# ProDocument_CSPS-ATX12VO-NAK12S20_2023-0.net
KiCad netlist of a schematic drawn in EasyEDA Pro
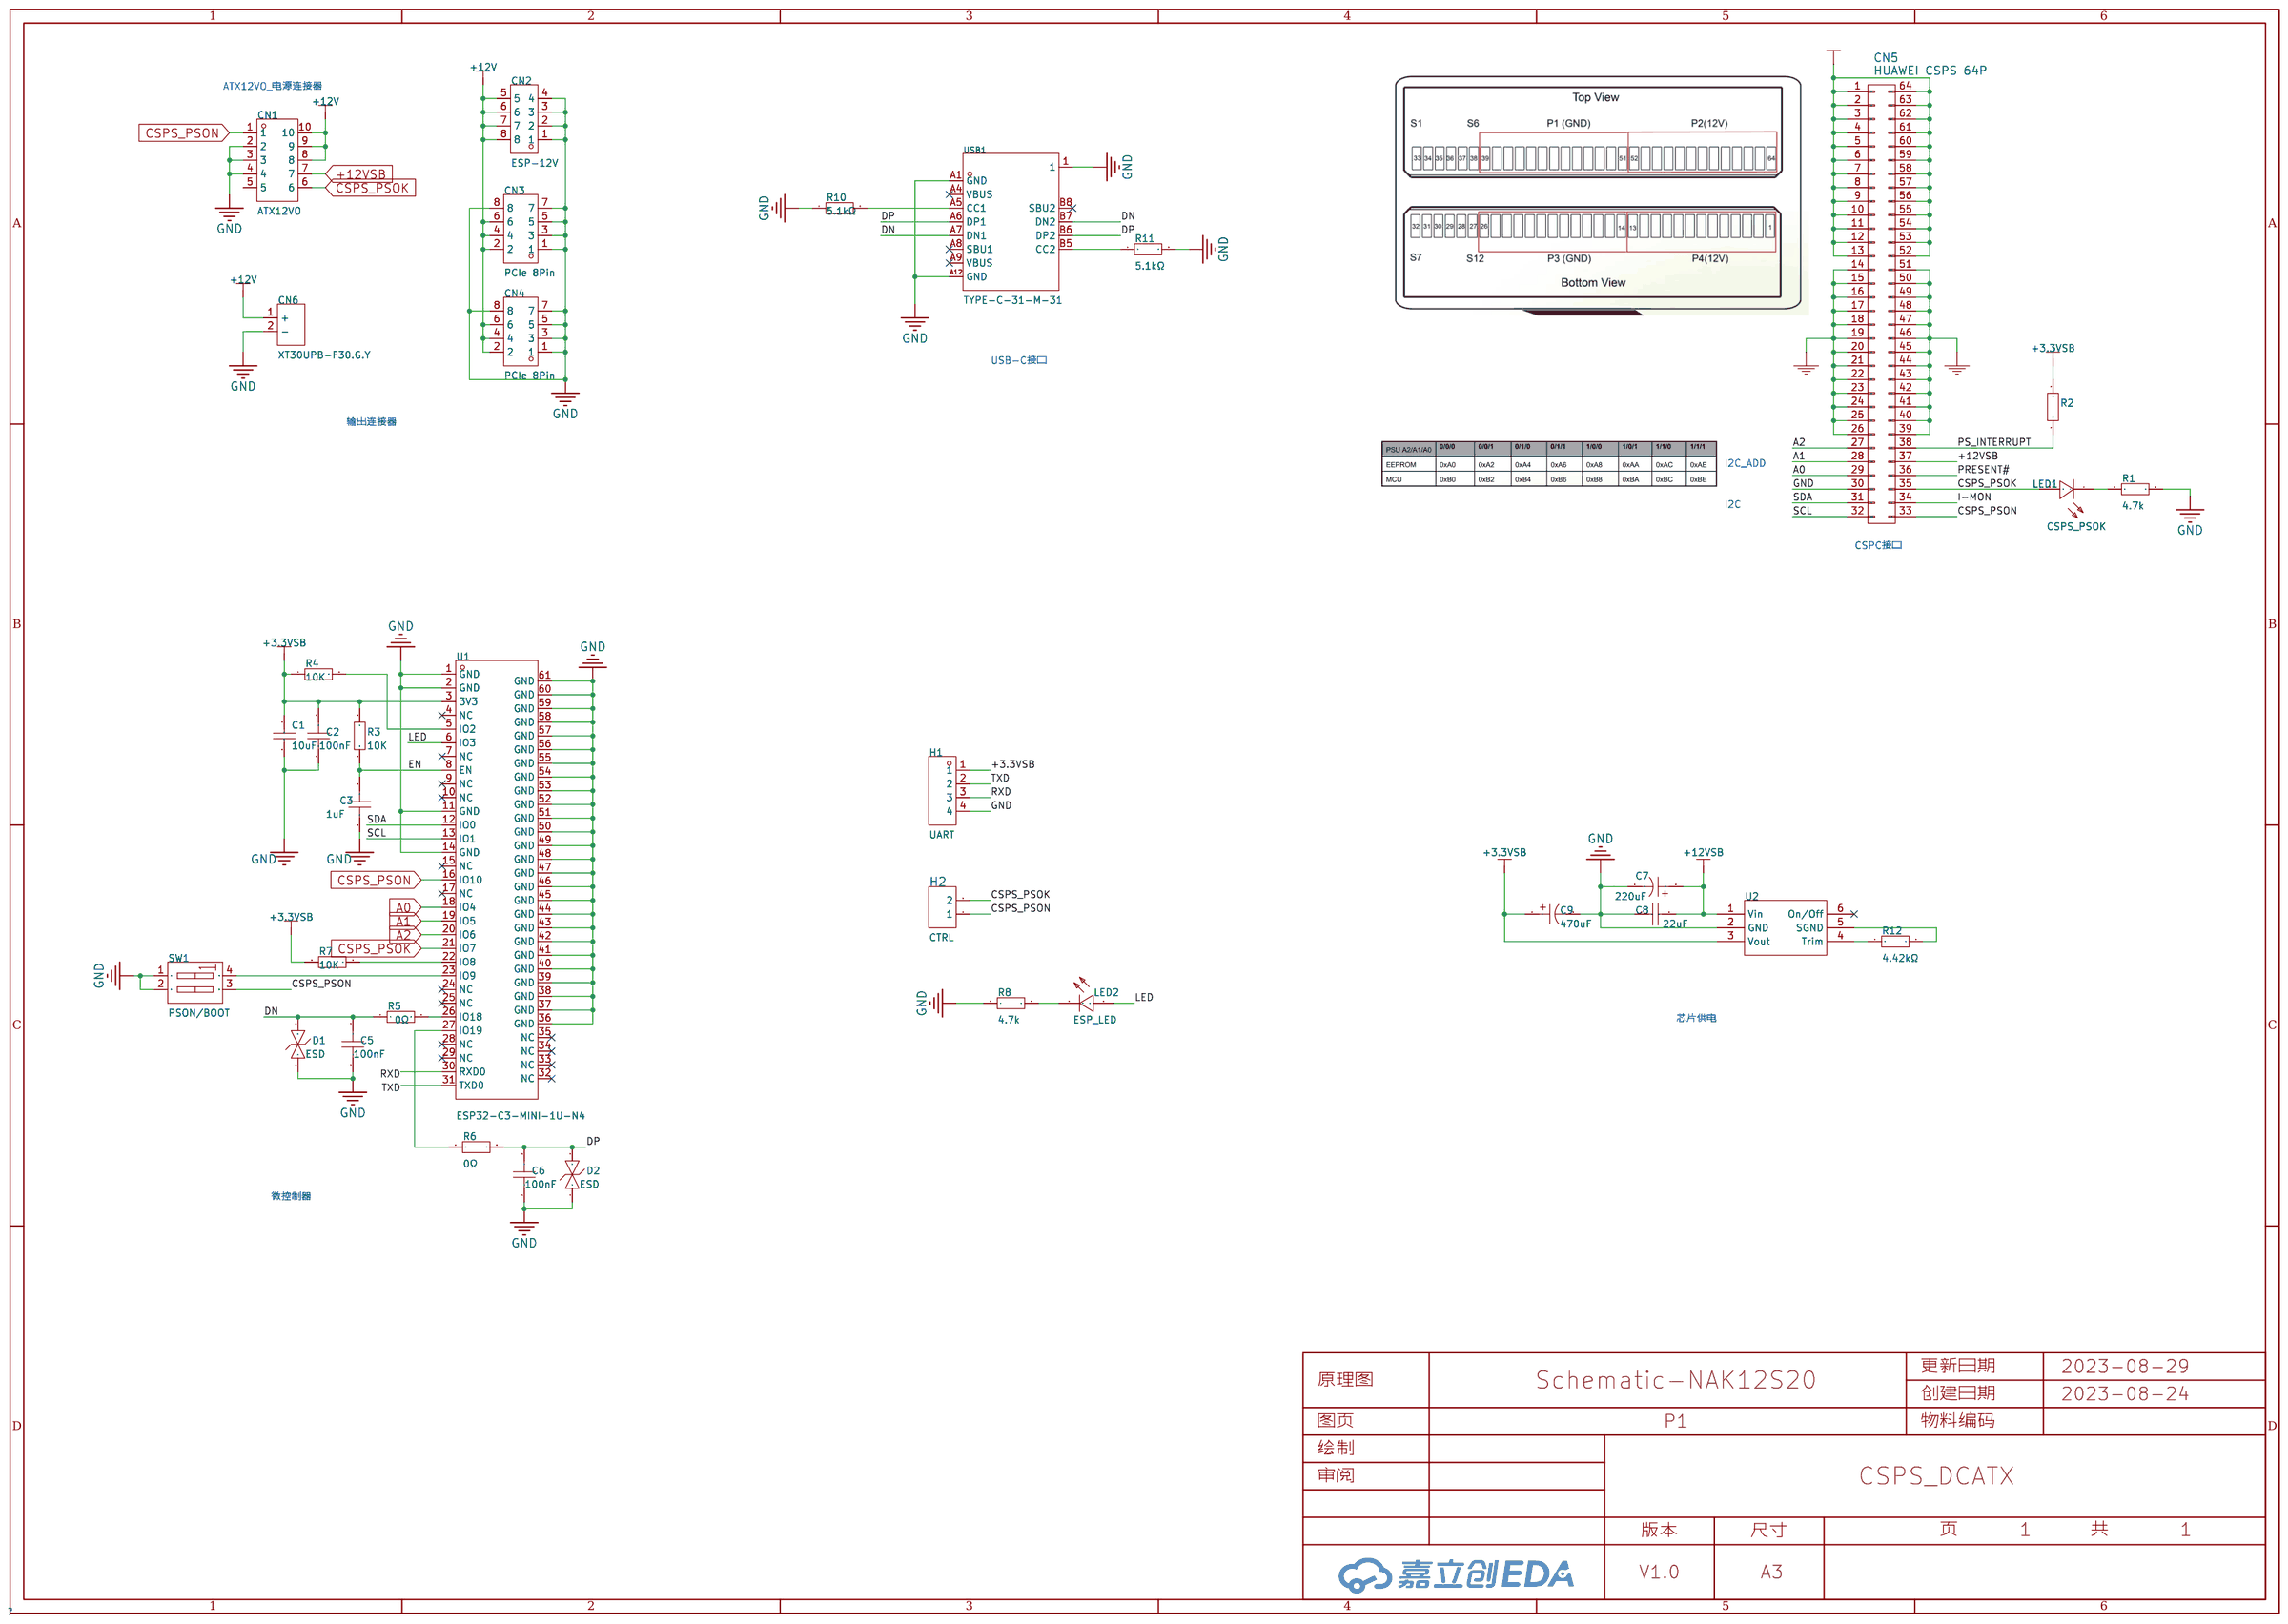
[diagram p0: schematic sheet]

(export (version "E")
  (design (tool "Eeschema 10.0.6"))
  (components
    (comp (ref "C1")
      (value "10uF")
      (footprint "easyedapro:C0805")
      (description "容值:10uF;精度:±10%;额定电压:25V;材质(温度系数):X5R;")
      (fields
        (field (name "Manufacturer Part") "CL21A106KAYNNNE")
        (field (name "Manufacturer") "SAMSUNG(三星)")
      )
      (libsource (lib "easyedapro") (part "CL21A106KAYNNNE"))
    )
    (comp (ref "C2")
      (value "100nF")
      (footprint "easyedapro:C0603")
      (libsource (lib "easyedapro") (part "CapAcitance"))
    )
    (comp (ref "C3")
      (value "1uF")
      (footprint "easyedapro:C0603")
      (libsource (lib "easyedapro") (part "CapAcitance"))
    )
    (comp (ref "C5")
      (value "100nF")
      (footprint "easyedapro:C0603")
      (libsource (lib "easyedapro") (part "CapAcitance"))
    )
    (comp (ref "C6")
      (value "100nF")
      (footprint "easyedapro:C0603")
      (libsource (lib "easyedapro") (part "CapAcitance"))
    )
    (comp (ref "C7")
      (value "220uF")
      (footprint "easyedapro:CAP-SMD_BD6.3-L6.6-W6.6-FD")
      (description "容值:220uF;精度:±20%;额定电压:16V;纹波电流:110mA@120Hz;等效串联电阻:-;")
      (fields
        (field (name "Manufacturer Part") "RVT220UF16V67RV0015")
        (field (name "Manufacturer") "KNSCHA(科尼盛)")
      )
      (libsource (lib "easyedapro") (part "RVT220UF16V67RV0015"))
    )
    (comp (ref "C8")
      (value "22uF")
      (footprint "easyedapro:C1206")
      (description "容值:22uF;精度:±10%;额定电压:25V;材质(温度系数):X5R;")
      (fields
        (field (name "Manufacturer Part") "CL31A226KAHNNNE")
        (field (name "Manufacturer") "SAMSUNG(三星)")
      )
      (libsource (lib "easyedapro") (part "CL31A226KAHNNNE"))
    )
    (comp (ref "C9")
      (value "470uF")
      (footprint "easyedapro:CAP-SMD_BD8.0-L8.3-W8.3-LS9.0-FD")
      (description "容值:470uF;额定电压:16V;工作寿命:2000hrs@105°C;")
      (fields
        (field (name "Manufacturer Part") "RVT470UF16V67RV0031")
        (field (name "Manufacturer") "KNSCHA(科尼盛)")
      )
      (libsource (lib "easyedapro") (part "RVT470UF16V67RV0031"))
    )
    (comp (ref "CN1")
      (value "ATX12VO")
      (footprint "easyedapro:CONN-TH_X9357WV-2-05-N2SN")
      (fields
        (field (name "Manufacturer Part") "X9357WV-2x05-N2SN")
        (field (name "Manufacturer") "XKB Connectivity(中国星坤)")
      )
      (libsource (lib "easyedapro") (part "X9357WV-2*05-N2SN"))
    )
    (comp (ref "CN2")
      (value "ESP-12V")
      (footprint "easyedapro:CONN-TH_39288080")
      (description "参考系列:-;间距:4.2mm;插针结构:2x4P;排数:2;每排PIN数:4;行距:4.2mm;公母:母型插口;安装方式:直插;额定电流:-;工作温度范围:-;")
      (fields (field (name "Manufacturer Part") "39288080") (field (name "Manufacturer") "MOLEX"))
      (libsource (lib "easyedapro") (part "39288080"))
    )
    (comp (ref "CN3")
      (value "PCIe 8Pin")
      (footprint "easyedapro:CONN-TH_8P-P4.20_CST_CS-1150-08D")
      (description "参考系列:-;间距:4.2mm;插针结构:2x4P;排数:2;每排PIN数:4;行距:4.2mm;公母:母型插口;安装方式:直插;额定电流:7A;工作温度范围:-40°C~+105°C;")
      (fields (field (name "Manufacturer Part") "CS-1150-08D") (field (name "Manufacturer") "CST(永丰盈)"))
      (libsource (lib "easyedapro") (part "CS-1150-08D"))
    )
    (comp (ref "CN4")
      (value "PCIe 8Pin")
      (footprint "easyedapro:CONN-TH_8P-P4.20_CST_CS-1150-08D")
      (description "参考系列:-;间距:4.2mm;插针结构:2x4P;排数:2;每排PIN数:4;行距:4.2mm;公母:母型插口;安装方式:直插;额定电流:7A;工作温度范围:-40°C~+105°C;")
      (fields (field (name "Manufacturer Part") "CS-1150-08D") (field (name "Manufacturer") "CST(永丰盈)"))
      (libsource (lib "easyedapro") (part "CS-1150-08D"))
    )
    (comp (ref "CN5")
      (value "HUAWEI CSPS 64P")
      (footprint "easyedapro:ATX 64P HP 野口64P直插")
      (libsource (lib "easyedapro") (part "HP CSPS ATX 64P"))
    )
    (comp (ref "CN6")
      (value "XT30UPB-F30.G.Y")
      (footprint "easyedapro:CONN-TH_XT30UPB-F")
      (description "模型插头连接器")
      (fields (field (name "Manufacturer") "AMASS(艾迈斯)"))
      (libsource (lib "easyedapro") (part "XT30UPB-F"))
    )
    (comp (ref "D1")
      (value "ESD")
      (footprint "easyedapro:SOD-882_L1.0-W0.6-BI")
      (description "极性:-;反向关断电压（典型值）:5V (Max);击穿电压（最小值）:6V;箝位电压:25V;峰值脉冲电流（10/1000us）:2.5A (8/20us);")
      (fields (field (name "Manufacturer Part") "ESD05V88D-LC") (field (name "Manufacturer") "SOCAY(硕凯)"))
      (libsource (lib "easyedapro") (part "ESD05V88D-LC"))
    )
    (comp (ref "D2")
      (value "ESD")
      (footprint "easyedapro:SOD-882_L1.0-W0.6-BI")
      (description "极性:-;反向关断电压（典型值）:5V (Max);击穿电压（最小值）:6V;箝位电压:25V;峰值脉冲电流（10/1000us）:2.5A (8/20us);")
      (fields (field (name "Manufacturer Part") "ESD05V88D-LC") (field (name "Manufacturer") "SOCAY(硕凯)"))
      (libsource (lib "easyedapro") (part "ESD05V88D-LC"))
    )
    (comp (ref "H1")
      (value "UART")
      (footprint "easyedapro:HDR-TH_4P-P2.54-V-F")
      (libsource (lib "easyedapro") (part "2.54-1*4P母"))
    )
    (comp (ref "H2")
      (value "CTRL")
      (footprint "easyedapro:HDR-TH_2P-P2.54-V-F")
      (libsource (lib "easyedapro") (part "Header-Female-2.54_1x2"))
    )
    (comp (ref "LED1")
      (value "CSPS_PSOK")
      (footprint "easyedapro:LED0603-RD_GREEN")
      (fields (field (name "Manufacturer Part") "LED-0603G-FZ_GREEN"))
      (libsource (lib "easyedapro") (part "LED-0603G-FZ_GREEN"))
    )
    (comp (ref "LED2")
      (value "ESP_LED")
      (footprint "easyedapro:LED0603-RD")
      (description "发光颜色:翠绿;二极管配置:-;主波长:520nm~535nm;色温:-;功率:110mW;安装方式:-;")
      (fields
        (field (name "Manufacturer Part") "19-217/GHC-YR1S2/3T")
        (field (name "Manufacturer") "EVERLIGHT(亿光)")
      )
      (libsource (lib "easyedapro") (part "19-217/GHC-YR1S2/3T"))
    )
    (comp (ref "R1") (value "4.7k") (footprint "easyedapro:R0603") (libsource (lib "easyedapro") (part "电阻")))
    (comp (ref "R2") (value "4.7k") (footprint "easyedapro:R0603") (libsource (lib "easyedapro") (part "电阻")))
    (comp (ref "R3") (value "10K") (footprint "easyedapro:R0603") (libsource (lib "easyedapro") (part "电阻")))
    (comp (ref "R4") (value "10K") (footprint "easyedapro:R0603") (libsource (lib "easyedapro") (part "电阻")))
    (comp (ref "R5")
      (value "0Ω")
      (footprint "easyedapro:R0603")
      (description "电阻类型:厚膜电阻;阻值:0Ω;精度:±1%;功率:100mW;")
      (fields
        (field (name "Manufacturer Part") "0603WAF0000T5E")
        (field (name "Manufacturer") "UNI-ROYAL(厚声)")
      )
      (libsource (lib "easyedapro") (part "0603WAF0000T5E"))
    )
    (comp (ref "R6")
      (value "0Ω")
      (footprint "easyedapro:R0603")
      (description "电阻类型:厚膜电阻;阻值:0Ω;精度:±1%;功率:100mW;")
      (fields
        (field (name "Manufacturer Part") "0603WAF0000T5E")
        (field (name "Manufacturer") "UNI-ROYAL(厚声)")
      )
      (libsource (lib "easyedapro") (part "0603WAF0000T5E"))
    )
    (comp (ref "R7") (value "10K") (footprint "easyedapro:R0603") (libsource (lib "easyedapro") (part "电阻")))
    (comp (ref "R8") (value "4.7k") (footprint "easyedapro:R0603") (libsource (lib "easyedapro") (part "电阻")))
    (comp (ref "R10")
      (value "5.1kΩ")
      (footprint "easyedapro:R0603")
      (description "电阻类型:厚膜电阻;阻值:5.1kΩ;精度:±1%;功率:100mW;")
      (fields
        (field (name "Manufacturer Part") "0603WAF5101T5E")
        (field (name "Manufacturer") "UNI-ROYAL(厚声)")
      )
      (libsource (lib "easyedapro") (part "0603WAF5101T5E"))
    )
    (comp (ref "R11")
      (value "5.1kΩ")
      (footprint "easyedapro:R0603")
      (description "电阻类型:厚膜电阻;阻值:5.1kΩ;精度:±1%;功率:100mW;")
      (fields
        (field (name "Manufacturer Part") "0603WAF5101T5E")
        (field (name "Manufacturer") "UNI-ROYAL(厚声)")
      )
      (libsource (lib "easyedapro") (part "0603WAF5101T5E"))
    )
    (comp (ref "R12")
      (value "4.42kΩ")
      (footprint "easyedapro:R0603")
      (description "电阻类型:厚膜电阻;阻值:4.42kΩ;精度:±1%;功率:100mW;")
      (fields
        (field (name "Manufacturer Part") "0603WAF4421T5E")
        (field (name "Manufacturer") "UNI-ROYAL(厚声)")
      )
      (libsource (lib "easyedapro") (part "0603WAF4421T5E"))
    )
    (comp (ref "SW1")
      (value "PSON/BOOT")
      (footprint "easyedapro:SW-SMD_4P-L6.0-W5.1-P2.54-LS9.3-BL")
      (description "类型:平拨，凸起式;电路结构:单刀单掷;开关位数:2;引脚间距:2.54mm;颜色:黑色;")
      (fields (field (name "Manufacturer Part") "DSIC02LSGET") (field (name "Manufacturer") "YE"))
      (libsource (lib "easyedapro") (part "DSIC02LSGET"))
    )
    (comp (ref "U1")
      (value "ESP32-C3-MINI-1U-N4")
      (footprint "easyedapro:WIFIM-SMD_61P-L13.2-W12.5-P0.80")
      (fields (field (name "Manufacturer") "ESPRESSIF(乐鑫)"))
      (libsource (lib "easyedapro") (part "ESP32-C3-MINI-1U-N4"))
    )
    (comp (ref "U2")
      (value "~")
      (footprint "easyedapro:NAK12S20-C")
      (description "华为降压模块")
      (fields (field (name "Manufacturer") "HUAWEI"))
      (libsource (lib "easyedapro") (part "NAK12S20-C"))
    )
    (comp (ref "USB1")
      (value "TYPE-C-31-M-31")
      (footprint "easyedapro:USB-C-SMD_TYPE-C-31-M-31")
      (description "连接器类型:Type-C;标准:-;公母:母座;触点数量:16;端口数量:1;安装方式:卧贴;额定电流 - 电源:5A;工作温度范围:-30°C~+80°C;")
      (fields (field (name "Manufacturer") "韩国韩荣"))
      (libsource (lib "easyedapro") (part "TYPE-C-31-M-31"))
    )
  )
  (nets
    (net (code "1") (name "+3.3VSB") (class "Default")
      (node (ref "C1") (pin "2") (pinfunction "2_2") (pintype "input"))
      (node (ref "C2") (pin "2") (pinfunction "2_2") (pintype "input"))
      (node (ref "C9") (pin "1") (pinfunction "1_1") (pintype "input"))
      (node (ref "H1") (pin "1") (pinfunction "1_1") (pintype "input"))
      (node (ref "R2") (pin "2") (pinfunction "2_2") (pintype "input"))
      (node (ref "R3") (pin "2") (pinfunction "2_2") (pintype "input"))
      (node (ref "R4") (pin "1") (pinfunction "1_1") (pintype "input"))
      (node (ref "R7") (pin "1") (pinfunction "1_1") (pintype "input"))
      (node (ref "U1") (pin "3") (pinfunction "3V3_3") (pintype "input"))
      (node (ref "U2") (pin "3") (pinfunction "Vout_3") (pintype "input"))
    )
    (net (code "2") (name "+12V") (class "Default")
      (node (ref "CN1") (pin "10") (pinfunction "10_10") (pintype "input"))
      (node (ref "CN1") (pin "8") (pinfunction "8_8") (pintype "input"))
      (node (ref "CN1") (pin "9") (pinfunction "9_9") (pintype "input"))
      (node (ref "CN2") (pin "5") (pinfunction "5_5") (pintype "input"))
      (node (ref "CN2") (pin "6") (pinfunction "6_6") (pintype "input"))
      (node (ref "CN2") (pin "7") (pinfunction "7_7") (pintype "input"))
      (node (ref "CN2") (pin "8") (pinfunction "8_8") (pintype "input"))
      (node (ref "CN3") (pin "2") (pinfunction "2_2") (pintype "input"))
      (node (ref "CN3") (pin "4") (pinfunction "4_4") (pintype "input"))
      (node (ref "CN3") (pin "6") (pinfunction "6_6") (pintype "input"))
      (node (ref "CN4") (pin "2") (pinfunction "2_2") (pintype "input"))
      (node (ref "CN4") (pin "4") (pinfunction "4_4") (pintype "input"))
      (node (ref "CN4") (pin "6") (pinfunction "6_6") (pintype "input"))
      (node (ref "CN5") (pin "1") (pinfunction "Pin_1_1") (pintype "input"))
      (node (ref "CN5") (pin "10") (pinfunction "Pin_10_10") (pintype "input"))
      (node (ref "CN5") (pin "11") (pinfunction "Pin_11_11") (pintype "input"))
      (node (ref "CN5") (pin "12") (pinfunction "Pin_12_12") (pintype "input"))
      (node (ref "CN5") (pin "13") (pinfunction "Pin_13_13") (pintype "input"))
      (node (ref "CN5") (pin "2") (pinfunction "Pin_2_2") (pintype "input"))
      (node (ref "CN5") (pin "3") (pinfunction "Pin_3_3") (pintype "input"))
      (node (ref "CN5") (pin "4") (pinfunction "Pin_4_4") (pintype "input"))
      (node (ref "CN5") (pin "5") (pinfunction "Pin_5_5") (pintype "input"))
      (node (ref "CN5") (pin "52") (pinfunction "Pin_52_52") (pintype "input"))
      (node (ref "CN5") (pin "53") (pinfunction "Pin_53_53") (pintype "input"))
      (node (ref "CN5") (pin "54") (pinfunction "Pin_54_54") (pintype "input"))
      (node (ref "CN5") (pin "55") (pinfunction "Pin_55_55") (pintype "input"))
      (node (ref "CN5") (pin "56") (pinfunction "Pin_56_56") (pintype "input"))
      (node (ref "CN5") (pin "57") (pinfunction "Pin_57_57") (pintype "input"))
      (node (ref "CN5") (pin "58") (pinfunction "Pin_58_58") (pintype "input"))
      (node (ref "CN5") (pin "59") (pinfunction "Pin_59_59") (pintype "input"))
      (node (ref "CN5") (pin "6") (pinfunction "Pin_6_6") (pintype "input"))
      (node (ref "CN5") (pin "60") (pinfunction "Pin_60_60") (pintype "input"))
      (node (ref "CN5") (pin "61") (pinfunction "Pin_61_61") (pintype "input"))
      (node (ref "CN5") (pin "62") (pinfunction "Pin_62_62") (pintype "input"))
      (node (ref "CN5") (pin "63") (pinfunction "Pin_63_63") (pintype "input"))
      (node (ref "CN5") (pin "64") (pinfunction "Pin_64_64") (pintype "input"))
      (node (ref "CN5") (pin "7") (pinfunction "Pin_7_7") (pintype "input"))
      (node (ref "CN5") (pin "8") (pinfunction "Pin_8_8") (pintype "input"))
      (node (ref "CN5") (pin "9") (pinfunction "Pin_9_9") (pintype "input"))
      (node (ref "CN6") (pin "1") (pinfunction "+_1") (pintype "input"))
    )
    (net (code "3") (name "+12VSB") (class "Default")
      (node (ref "C7") (pin "1") (pinfunction "1_1") (pintype "input"))
      (node (ref "C8") (pin "2") (pinfunction "2_2") (pintype "input"))
      (node (ref "CN1") (pin "7") (pinfunction "7_7") (pintype "input"))
      (node (ref "CN5") (pin "37") (pinfunction "+12VSB_37") (pintype "input"))
      (node (ref "U2") (pin "1") (pinfunction "Vin_1") (pintype "input"))
    )
    (net (code "4") (name "/DN") (class "Default")
      (node (ref "C5") (pin "2") (pinfunction "2_2") (pintype "input"))
      (node (ref "D1") (pin "2") (pinfunction "2_2") (pintype "input"))
      (node (ref "R5") (pin "1") (pinfunction "1_1") (pintype "input"))
      (node (ref "USB1") (pin "A7") (pinfunction "DN1_A7") (pintype "input"))
      (node (ref "USB1") (pin "B7") (pinfunction "DN2_B7") (pintype "input"))
    )
    (net (code "5") (name "/DP") (class "Default")
      (node (ref "C6") (pin "2") (pinfunction "2_2") (pintype "input"))
      (node (ref "D2") (pin "2") (pinfunction "2_2") (pintype "input"))
      (node (ref "R6") (pin "2") (pinfunction "2_2") (pintype "input"))
      (node (ref "USB1") (pin "A6") (pinfunction "DP1_A6") (pintype "input"))
      (node (ref "USB1") (pin "B6") (pinfunction "DP2_B6") (pintype "input"))
    )
    (net (code "6") (name "/EN") (class "Default")
      (node (ref "C3") (pin "2") (pinfunction "2_2") (pintype "input"))
      (node (ref "R3") (pin "1") (pinfunction "1_1") (pintype "input"))
      (node (ref "U1") (pin "8") (pinfunction "EN_8") (pintype "input"))
    )
    (net (code "7") (name "/I-MON") (class "Default")
      (node (ref "CN5") (pin "34") (pinfunction "sda_34") (pintype "input"))
    )
    (net (code "8") (name "/LED") (class "Default")
      (node (ref "LED2") (pin "2") (pinfunction "A_2") (pintype "input"))
      (node (ref "U1") (pin "6") (pinfunction "IO3_6") (pintype "input"))
    )
    (net (code "9") (name "/PRESENT#") (class "Default")
      (node (ref "CN5") (pin "36") (pinfunction "PRESENT_36") (pintype "input"))
    )
    (net (code "10") (name "/PS_INTERRUPT") (class "Default")
      (node (ref "CN5") (pin "38") (pinfunction "pin_38_38") (pintype "input"))
      (node (ref "R2") (pin "1") (pinfunction "1_1") (pintype "input"))
    )
    (net (code "11") (name "/RXD") (class "Default")
      (node (ref "H1") (pin "3") (pinfunction "3_3") (pintype "input"))
      (node (ref "U1") (pin "30") (pinfunction "RXD0_30") (pintype "input"))
    )
    (net (code "12") (name "/SCL") (class "Default")
      (node (ref "CN5") (pin "32") (pinfunction "CSPS-PSON_32") (pintype "input"))
      (node (ref "U1") (pin "13") (pinfunction "IO1_13") (pintype "input"))
    )
    (net (code "13") (name "/SDA") (class "Default")
      (node (ref "CN5") (pin "31") (pinfunction "Pin_31_31") (pintype "input"))
      (node (ref "U1") (pin "12") (pinfunction "IO0_12") (pintype "input"))
    )
    (net (code "14") (name "/TXD") (class "Default")
      (node (ref "H1") (pin "2") (pinfunction "2_2") (pintype "input"))
      (node (ref "U1") (pin "31") (pinfunction "TXD0_31") (pintype "input"))
    )
    (net (code "15") (name "A0") (class "Default")
      (node (ref "CN5") (pin "29") (pinfunction "PRESENT_29") (pintype "input"))
      (node (ref "U1") (pin "18") (pinfunction "IO4_18") (pintype "input"))
    )
    (net (code "16") (name "A1") (class "Default")
      (node (ref "CN5") (pin "28") (pinfunction "+12VSB_28") (pintype "input"))
      (node (ref "U1") (pin "19") (pinfunction "IO5_19") (pintype "input"))
    )
    (net (code "17") (name "A2") (class "Default")
      (node (ref "CN5") (pin "27") (pinfunction "PWOK_27") (pintype "input"))
      (node (ref "U1") (pin "20") (pinfunction "IO6_20") (pintype "input"))
    )
    (net (code "18") (name "CSPS_PSOK") (class "Default")
      (node (ref "CN1") (pin "6") (pinfunction "6_6") (pintype "input"))
      (node (ref "CN5") (pin "35") (pinfunction "I2C-GND_35") (pintype "input"))
      (node (ref "H2") (pin "2") (pinfunction "2_2") (pintype "input"))
      (node (ref "LED1") (pin "2") (pinfunction "+_2") (pintype "input"))
      (node (ref "U1") (pin "21") (pinfunction "IO7_21") (pintype "input"))
    )
    (net (code "19") (name "CSPS_PSON") (class "Default")
      (node (ref "CN1") (pin "1") (pinfunction "1_1") (pintype "input"))
      (node (ref "CN5") (pin "33") (pinfunction "scl_33") (pintype "input"))
      (node (ref "H2") (pin "1") (pinfunction "1_1") (pintype "input"))
      (node (ref "SW1") (pin "3") (pinfunction "B2_3") (pintype "input"))
      (node (ref "U1") (pin "16") (pinfunction "IO10_16") (pintype "input"))
    )
    (net (code "20") (name "GND") (class "Default")
      (node (ref "C1") (pin "1") (pinfunction "1_1") (pintype "input"))
      (node (ref "C2") (pin "1") (pinfunction "1_1") (pintype "input"))
      (node (ref "C3") (pin "1") (pinfunction "1_1") (pintype "input"))
      (node (ref "C5") (pin "1") (pinfunction "1_1") (pintype "input"))
      (node (ref "C6") (pin "1") (pinfunction "1_1") (pintype "input"))
      (node (ref "C7") (pin "2") (pinfunction "2_2") (pintype "input"))
      (node (ref "C8") (pin "1") (pinfunction "1_1") (pintype "input"))
      (node (ref "C9") (pin "2") (pinfunction "2_2") (pintype "input"))
      (node (ref "CN1") (pin "2") (pinfunction "2_2") (pintype "input"))
      (node (ref "CN1") (pin "3") (pinfunction "3_3") (pintype "input"))
      (node (ref "CN1") (pin "4") (pinfunction "4_4") (pintype "input"))
      (node (ref "CN2") (pin "1") (pinfunction "1_1") (pintype "input"))
      (node (ref "CN2") (pin "2") (pinfunction "2_2") (pintype "input"))
      (node (ref "CN2") (pin "3") (pinfunction "3_3") (pintype "input"))
      (node (ref "CN2") (pin "4") (pinfunction "4_4") (pintype "input"))
      (node (ref "CN3") (pin "1") (pinfunction "1_1") (pintype "input"))
      (node (ref "CN3") (pin "3") (pinfunction "3_3") (pintype "input"))
      (node (ref "CN3") (pin "5") (pinfunction "5_5") (pintype "input"))
      (node (ref "CN3") (pin "7") (pinfunction "7_7") (pintype "input"))
      (node (ref "CN3") (pin "8") (pinfunction "8_8") (pintype "input"))
      (node (ref "CN4") (pin "1") (pinfunction "1_1") (pintype "input"))
      (node (ref "CN4") (pin "3") (pinfunction "3_3") (pintype "input"))
      (node (ref "CN4") (pin "5") (pinfunction "5_5") (pintype "input"))
      (node (ref "CN4") (pin "7") (pinfunction "7_7") (pintype "input"))
      (node (ref "CN4") (pin "8") (pinfunction "8_8") (pintype "input"))
      (node (ref "CN5") (pin "14") (pinfunction "Pin_14_14") (pintype "input"))
      (node (ref "CN5") (pin "15") (pinfunction "Pin_15_15") (pintype "input"))
      (node (ref "CN5") (pin "16") (pinfunction "Pin_16_16") (pintype "input"))
      (node (ref "CN5") (pin "17") (pinfunction "Pin_17_17") (pintype "input"))
      (node (ref "CN5") (pin "18") (pinfunction "Pin_18_18") (pintype "input"))
      (node (ref "CN5") (pin "19") (pinfunction "Pin_19_19") (pintype "input"))
      (node (ref "CN5") (pin "20") (pinfunction "Pin_20_20") (pintype "input"))
      (node (ref "CN5") (pin "21") (pinfunction "Pin_21_21") (pintype "input"))
      (node (ref "CN5") (pin "22") (pinfunction "Pin_22_22") (pintype "input"))
      (node (ref "CN5") (pin "23") (pinfunction "Pin_23_23") (pintype "input"))
      (node (ref "CN5") (pin "24") (pinfunction "Pin_24_24") (pintype "input"))
      (node (ref "CN5") (pin "25") (pinfunction "Pin_25_25") (pintype "input"))
      (node (ref "CN5") (pin "26") (pinfunction "Pin_26_26") (pintype "input"))
      (node (ref "CN5") (pin "30") (pinfunction "CSPS-PSOK_30") (pintype "input"))
      (node (ref "CN5") (pin "39") (pinfunction "Pin_39_39") (pintype "input"))
      (node (ref "CN5") (pin "40") (pinfunction "Pin_40_40") (pintype "input"))
      (node (ref "CN5") (pin "41") (pinfunction "Pin_41_41") (pintype "input"))
      (node (ref "CN5") (pin "42") (pinfunction "Pin_42_42") (pintype "input"))
      (node (ref "CN5") (pin "43") (pinfunction "Pin_43_43") (pintype "input"))
      (node (ref "CN5") (pin "44") (pinfunction "Pin_44_44") (pintype "input"))
      (node (ref "CN5") (pin "45") (pinfunction "Pin_45_45") (pintype "input"))
      (node (ref "CN5") (pin "46") (pinfunction "Pin_46_46") (pintype "input"))
      (node (ref "CN5") (pin "47") (pinfunction "Pin_47_47") (pintype "input"))
      (node (ref "CN5") (pin "48") (pinfunction "Pin_48_48") (pintype "input"))
      (node (ref "CN5") (pin "49") (pinfunction "Pin_49_49") (pintype "input"))
      (node (ref "CN5") (pin "50") (pinfunction "Pin_50_50") (pintype "input"))
      (node (ref "CN5") (pin "51") (pinfunction "Pin_51_51") (pintype "input"))
      (node (ref "CN6") (pin "2") (pinfunction "-_2") (pintype "input"))
      (node (ref "D1") (pin "1") (pinfunction "1_1") (pintype "input"))
      (node (ref "D2") (pin "1") (pinfunction "1_1") (pintype "input"))
      (node (ref "H1") (pin "4") (pinfunction "4_4") (pintype "input"))
      (node (ref "R1") (pin "2") (pinfunction "2_2") (pintype "input"))
      (node (ref "R10") (pin "1") (pinfunction "1_1") (pintype "input"))
      (node (ref "R11") (pin "2") (pinfunction "2_2") (pintype "input"))
      (node (ref "R8") (pin "1") (pinfunction "1_1") (pintype "input"))
      (node (ref "SW1") (pin "1") (pinfunction "A1_1") (pintype "input"))
      (node (ref "SW1") (pin "2") (pinfunction "A2_2") (pintype "input"))
      (node (ref "U1") (pin "1") (pinfunction "GND_1") (pintype "input"))
      (node (ref "U1") (pin "11") (pinfunction "GND_11") (pintype "input"))
      (node (ref "U1") (pin "14") (pinfunction "GND_14") (pintype "input"))
      (node (ref "U1") (pin "2") (pinfunction "GND_2") (pintype "input"))
      (node (ref "U1") (pin "36") (pinfunction "GND_36") (pintype "input"))
      (node (ref "U1") (pin "37") (pinfunction "GND_37") (pintype "input"))
      (node (ref "U1") (pin "38") (pinfunction "GND_38") (pintype "input"))
      (node (ref "U1") (pin "39") (pinfunction "GND_39") (pintype "input"))
      (node (ref "U1") (pin "40") (pinfunction "GND_40") (pintype "input"))
      (node (ref "U1") (pin "41") (pinfunction "GND_41") (pintype "input"))
      (node (ref "U1") (pin "42") (pinfunction "GND_42") (pintype "input"))
      (node (ref "U1") (pin "43") (pinfunction "GND_43") (pintype "input"))
      (node (ref "U1") (pin "44") (pinfunction "GND_44") (pintype "input"))
      (node (ref "U1") (pin "45") (pinfunction "GND_45") (pintype "input"))
      (node (ref "U1") (pin "46") (pinfunction "GND_46") (pintype "input"))
      (node (ref "U1") (pin "47") (pinfunction "GND_47") (pintype "input"))
      (node (ref "U1") (pin "48") (pinfunction "GND_48") (pintype "input"))
      (node (ref "U1") (pin "49") (pinfunction "GND_49") (pintype "input"))
      (node (ref "U1") (pin "50") (pinfunction "GND_50") (pintype "input"))
      (node (ref "U1") (pin "51") (pinfunction "GND_51") (pintype "input"))
      (node (ref "U1") (pin "52") (pinfunction "GND_52") (pintype "input"))
      (node (ref "U1") (pin "53") (pinfunction "GND_53") (pintype "input"))
      (node (ref "U1") (pin "54") (pinfunction "GND_54") (pintype "input"))
      (node (ref "U1") (pin "55") (pinfunction "GND_55") (pintype "input"))
      (node (ref "U1") (pin "56") (pinfunction "GND_56") (pintype "input"))
      (node (ref "U1") (pin "57") (pinfunction "GND_57") (pintype "input"))
      (node (ref "U1") (pin "58") (pinfunction "GND_58") (pintype "input"))
      (node (ref "U1") (pin "59") (pinfunction "GND_59") (pintype "input"))
      (node (ref "U1") (pin "60") (pinfunction "GND_60") (pintype "input"))
      (node (ref "U1") (pin "61") (pinfunction "GND_61") (pintype "input"))
      (node (ref "U2") (pin "2") (pinfunction "GND_2") (pintype "input"))
      (node (ref "USB1") (pin "1") (pinfunction "1_1") (pintype "input"))
      (node (ref "USB1") (pin "A1") (pinfunction "GND_A1") (pintype "input"))
      (node (ref "USB1") (pin "A12") (pinfunction "GND_A12") (pintype "input"))
    )
    (net (code "21") (name "Net-(LED1--)") (class "Default")
      (node (ref "LED1") (pin "1") (pinfunction "-_1") (pintype "input"))
      (node (ref "R1") (pin "1") (pinfunction "1_1") (pintype "input"))
    )
    (net (code "22") (name "Net-(LED2-C)") (class "Default")
      (node (ref "LED2") (pin "1") (pinfunction "C_1") (pintype "input"))
      (node (ref "R8") (pin "2") (pinfunction "2_2") (pintype "input"))
    )
    (net (code "23") (name "Net-(SW1-B1)") (class "Default")
      (node (ref "SW1") (pin "4") (pinfunction "B1_4") (pintype "input"))
      (node (ref "U1") (pin "23") (pinfunction "IO9_23") (pintype "input"))
    )
    (net (code "24") (name "Net-(U1-IO2)") (class "Default")
      (node (ref "R4") (pin "2") (pinfunction "2_2") (pintype "input"))
      (node (ref "U1") (pin "5") (pinfunction "IO2_5") (pintype "input"))
    )
    (net (code "25") (name "Net-(U1-IO8)") (class "Default")
      (node (ref "R7") (pin "2") (pinfunction "2_2") (pintype "input"))
      (node (ref "U1") (pin "22") (pinfunction "IO8_22") (pintype "input"))
    )
    (net (code "26") (name "Net-(U1-IO18)") (class "Default")
      (node (ref "R5") (pin "2") (pinfunction "2_2") (pintype "input"))
      (node (ref "U1") (pin "26") (pinfunction "IO18_26") (pintype "input"))
    )
    (net (code "27") (name "Net-(U1-IO19)") (class "Default")
      (node (ref "R6") (pin "1") (pinfunction "1_1") (pintype "input"))
      (node (ref "U1") (pin "27") (pinfunction "IO19_27") (pintype "input"))
    )
    (net (code "28") (name "Net-(U2-SGND)") (class "Default")
      (node (ref "R12") (pin "2") (pinfunction "2_2") (pintype "input"))
      (node (ref "U2") (pin "5") (pinfunction "SGND_5") (pintype "input"))
    )
    (net (code "29") (name "Net-(U2-Trim)") (class "Default")
      (node (ref "R12") (pin "1") (pinfunction "1_1") (pintype "input"))
      (node (ref "U2") (pin "4") (pinfunction "Trim_4") (pintype "input"))
    )
    (net (code "30") (name "Net-(USB1-CC1)") (class "Default")
      (node (ref "R10") (pin "2") (pinfunction "2_2") (pintype "input"))
      (node (ref "USB1") (pin "A5") (pinfunction "CC1_A5") (pintype "input"))
    )
    (net (code "31") (name "Net-(USB1-CC2)") (class "Default")
      (node (ref "R11") (pin "1") (pinfunction "1_1") (pintype "input"))
      (node (ref "USB1") (pin "B5") (pinfunction "CC2_B5") (pintype "input"))
    )
    (net (code "32") (name "unconnected-(CN1-Pad5)") (class "Default")
      (node (ref "CN1") (pin "5") (pinfunction "5_5") (pintype "input"))
    )
    (net (code "33") (name "unconnected-(U1-NC-Pad4)") (class "Default")
      (node (ref "U1") (pin "4") (pinfunction "NC_4") (pintype "input+no_connect"))
    )
    (net (code "34") (name "unconnected-(U1-NC-Pad7)") (class "Default")
      (node (ref "U1") (pin "7") (pinfunction "NC_7") (pintype "input+no_connect"))
    )
    (net (code "35") (name "unconnected-(U1-NC-Pad9)") (class "Default")
      (node (ref "U1") (pin "9") (pinfunction "NC_9") (pintype "input+no_connect"))
    )
    (net (code "36") (name "unconnected-(U1-NC-Pad10)") (class "Default")
      (node (ref "U1") (pin "10") (pinfunction "NC_10") (pintype "input+no_connect"))
    )
    (net (code "37") (name "unconnected-(U1-NC-Pad15)") (class "Default")
      (node (ref "U1") (pin "15") (pinfunction "NC_15") (pintype "input+no_connect"))
    )
    (net (code "38") (name "unconnected-(U1-NC-Pad17)") (class "Default")
      (node (ref "U1") (pin "17") (pinfunction "NC_17") (pintype "input+no_connect"))
    )
    (net (code "39") (name "unconnected-(U1-NC-Pad24)") (class "Default")
      (node (ref "U1") (pin "24") (pinfunction "NC_24") (pintype "input+no_connect"))
    )
    (net (code "40") (name "unconnected-(U1-NC-Pad25)") (class "Default")
      (node (ref "U1") (pin "25") (pinfunction "NC_25") (pintype "input+no_connect"))
    )
    (net (code "41") (name "unconnected-(U1-NC-Pad28)") (class "Default")
      (node (ref "U1") (pin "28") (pinfunction "NC_28") (pintype "input+no_connect"))
    )
    (net (code "42") (name "unconnected-(U1-NC-Pad29)") (class "Default")
      (node (ref "U1") (pin "29") (pinfunction "NC_29") (pintype "input+no_connect"))
    )
    (net (code "43") (name "unconnected-(U1-NC-Pad32)") (class "Default")
      (node (ref "U1") (pin "32") (pinfunction "NC_32") (pintype "input+no_connect"))
    )
    (net (code "44") (name "unconnected-(U1-NC-Pad33)") (class "Default")
      (node (ref "U1") (pin "33") (pinfunction "NC_33") (pintype "input+no_connect"))
    )
    (net (code "45") (name "unconnected-(U1-NC-Pad34)") (class "Default")
      (node (ref "U1") (pin "34") (pinfunction "NC_34") (pintype "input+no_connect"))
    )
    (net (code "46") (name "unconnected-(U1-NC-Pad35)") (class "Default")
      (node (ref "U1") (pin "35") (pinfunction "NC_35") (pintype "input+no_connect"))
    )
    (net (code "47") (name "unconnected-(U2-On{slash}Off-Pad6)") (class "Default")
      (node (ref "U2") (pin "6") (pinfunction "On/Off_6") (pintype "input+no_connect"))
    )
    (net (code "48") (name "unconnected-(USB1-SBU1-PadA8)") (class "Default")
      (node (ref "USB1") (pin "A8") (pinfunction "SBU1_A8") (pintype "input+no_connect"))
    )
    (net (code "49") (name "unconnected-(USB1-SBU2-PadB8)") (class "Default")
      (node (ref "USB1") (pin "B8") (pinfunction "SBU2_B8") (pintype "input+no_connect"))
    )
    (net (code "50") (name "unconnected-(USB1-VBUS-PadA4)") (class "Default")
      (node (ref "USB1") (pin "A4") (pinfunction "VBUS_A4") (pintype "input+no_connect"))
    )
    (net (code "51") (name "unconnected-(USB1-VBUS-PadA9)") (class "Default")
      (node (ref "USB1") (pin "A9") (pinfunction "VBUS_A9") (pintype "input+no_connect"))
    )
  )
)
